# Keypad.net
KiCad netlist of a schematic drawn in Altium Designer
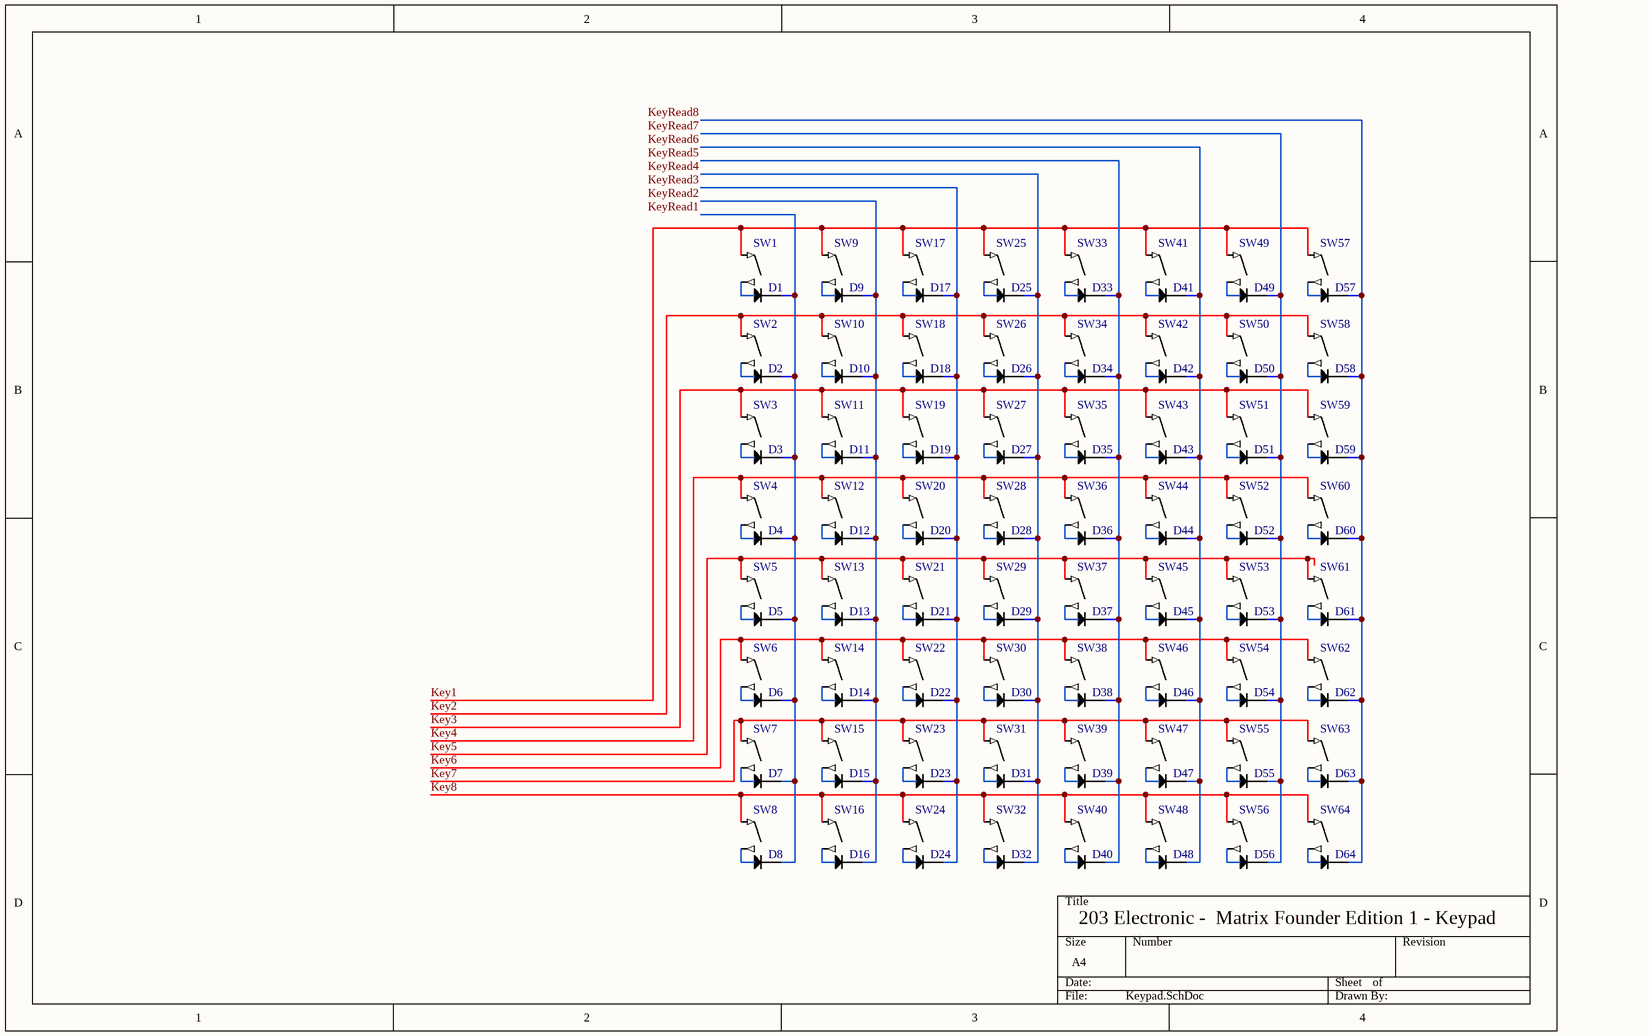
[diagram p0: Keypad.SchDoc]

(export (version "E")
  (design (tool "Eeschema 10.0.6"))
  (components
    (comp (ref "D1") (value "1N4148") (footprint "SOD123") (libsource (lib "Project 64") (part "1N4148")))
    (comp (ref "D2") (value "1N4148") (footprint "SOD123") (libsource (lib "Project 64") (part "1N4148")))
    (comp (ref "D3") (value "1N4148") (footprint "SOD123") (libsource (lib "Project 64") (part "1N4148")))
    (comp (ref "D4") (value "1N4148") (footprint "SOD123") (libsource (lib "Project 64") (part "1N4148")))
    (comp (ref "D5") (value "1N4148") (footprint "SOD123") (libsource (lib "Project 64") (part "1N4148")))
    (comp (ref "D6") (value "1N4148") (footprint "SOD123") (libsource (lib "Project 64") (part "1N4148")))
    (comp (ref "D7") (value "1N4148") (footprint "SOD123") (libsource (lib "Project 64") (part "1N4148")))
    (comp (ref "D8") (value "1N4148") (footprint "SOD123") (libsource (lib "Project 64") (part "1N4148")))
    (comp (ref "D9") (value "1N4148") (footprint "SOD123") (libsource (lib "Project 64") (part "1N4148")))
    (comp (ref "D10") (value "1N4148") (footprint "SOD123") (libsource (lib "Project 64") (part "1N4148")))
    (comp (ref "D11") (value "1N4148") (footprint "SOD123") (libsource (lib "Project 64") (part "1N4148")))
    (comp (ref "D12") (value "1N4148") (footprint "SOD123") (libsource (lib "Project 64") (part "1N4148")))
    (comp (ref "D13") (value "1N4148") (footprint "SOD123") (libsource (lib "Project 64") (part "1N4148")))
    (comp (ref "D14") (value "1N4148") (footprint "SOD123") (libsource (lib "Project 64") (part "1N4148")))
    (comp (ref "D15") (value "1N4148") (footprint "SOD123") (libsource (lib "Project 64") (part "1N4148")))
    (comp (ref "D16") (value "1N4148") (footprint "SOD123") (libsource (lib "Project 64") (part "1N4148")))
    (comp (ref "D17") (value "1N4148") (footprint "SOD123") (libsource (lib "Project 64") (part "1N4148")))
    (comp (ref "D18") (value "1N4148") (footprint "SOD123") (libsource (lib "Project 64") (part "1N4148")))
    (comp (ref "D19") (value "1N4148") (footprint "SOD123") (libsource (lib "Project 64") (part "1N4148")))
    (comp (ref "D20") (value "1N4148") (footprint "SOD123") (libsource (lib "Project 64") (part "1N4148")))
    (comp (ref "D21") (value "1N4148") (footprint "SOD123") (libsource (lib "Project 64") (part "1N4148")))
    (comp (ref "D22") (value "1N4148") (footprint "SOD123") (libsource (lib "Project 64") (part "1N4148")))
    (comp (ref "D23") (value "1N4148") (footprint "SOD123") (libsource (lib "Project 64") (part "1N4148")))
    (comp (ref "D24") (value "1N4148") (footprint "SOD123") (libsource (lib "Project 64") (part "1N4148")))
    (comp (ref "D25") (value "1N4148") (footprint "SOD123") (libsource (lib "Project 64") (part "1N4148")))
    (comp (ref "D26") (value "1N4148") (footprint "SOD123") (libsource (lib "Project 64") (part "1N4148")))
    (comp (ref "D27") (value "1N4148") (footprint "SOD123") (libsource (lib "Project 64") (part "1N4148")))
    (comp (ref "D28") (value "1N4148") (footprint "SOD123") (libsource (lib "Project 64") (part "1N4148")))
    (comp (ref "D29") (value "1N4148") (footprint "SOD123") (libsource (lib "Project 64") (part "1N4148")))
    (comp (ref "D30") (value "1N4148") (footprint "SOD123") (libsource (lib "Project 64") (part "1N4148")))
    (comp (ref "D31") (value "1N4148") (footprint "SOD123") (libsource (lib "Project 64") (part "1N4148")))
    (comp (ref "D32") (value "1N4148") (footprint "SOD123") (libsource (lib "Project 64") (part "1N4148")))
    (comp (ref "D33") (value "1N4148") (footprint "SOD123") (libsource (lib "Project 64") (part "1N4148")))
    (comp (ref "D34") (value "1N4148") (footprint "SOD123") (libsource (lib "Project 64") (part "1N4148")))
    (comp (ref "D35") (value "1N4148") (footprint "SOD123") (libsource (lib "Project 64") (part "1N4148")))
    (comp (ref "D36") (value "1N4148") (footprint "SOD123") (libsource (lib "Project 64") (part "1N4148")))
    (comp (ref "D37") (value "1N4148") (footprint "SOD123") (libsource (lib "Project 64") (part "1N4148")))
    (comp (ref "D38") (value "1N4148") (footprint "SOD123") (libsource (lib "Project 64") (part "1N4148")))
    (comp (ref "D39") (value "1N4148") (footprint "SOD123") (libsource (lib "Project 64") (part "1N4148")))
    (comp (ref "D40") (value "1N4148") (footprint "SOD123") (libsource (lib "Project 64") (part "1N4148")))
    (comp (ref "D41") (value "1N4148") (footprint "SOD123") (libsource (lib "Project 64") (part "1N4148")))
    (comp (ref "D42") (value "1N4148") (footprint "SOD123") (libsource (lib "Project 64") (part "1N4148")))
    (comp (ref "D43") (value "1N4148") (footprint "SOD123") (libsource (lib "Project 64") (part "1N4148")))
    (comp (ref "D44") (value "1N4148") (footprint "SOD123") (libsource (lib "Project 64") (part "1N4148")))
    (comp (ref "D45") (value "1N4148") (footprint "SOD123") (libsource (lib "Project 64") (part "1N4148")))
    (comp (ref "D46") (value "1N4148") (footprint "SOD123") (libsource (lib "Project 64") (part "1N4148")))
    (comp (ref "D47") (value "1N4148") (footprint "SOD123") (libsource (lib "Project 64") (part "1N4148")))
    (comp (ref "D48") (value "1N4148") (footprint "SOD123") (libsource (lib "Project 64") (part "1N4148")))
    (comp (ref "D49") (value "1N4148") (footprint "SOD123") (libsource (lib "Project 64") (part "1N4148")))
    (comp (ref "D50") (value "1N4148") (footprint "SOD123") (libsource (lib "Project 64") (part "1N4148")))
    (comp (ref "D51") (value "1N4148") (footprint "SOD123") (libsource (lib "Project 64") (part "1N4148")))
    (comp (ref "D52") (value "1N4148") (footprint "SOD123") (libsource (lib "Project 64") (part "1N4148")))
    (comp (ref "D53") (value "1N4148") (footprint "SOD123") (libsource (lib "Project 64") (part "1N4148")))
    (comp (ref "D54") (value "1N4148") (footprint "SOD123") (libsource (lib "Project 64") (part "1N4148")))
    (comp (ref "D55") (value "1N4148") (footprint "SOD123") (libsource (lib "Project 64") (part "1N4148")))
    (comp (ref "D56") (value "1N4148") (footprint "SOD123") (libsource (lib "Project 64") (part "1N4148")))
    (comp (ref "D57") (value "1N4148") (footprint "SOD123") (libsource (lib "Project 64") (part "1N4148")))
    (comp (ref "D58") (value "1N4148") (footprint "SOD123") (libsource (lib "Project 64") (part "1N4148")))
    (comp (ref "D59") (value "1N4148") (footprint "SOD123") (libsource (lib "Project 64") (part "1N4148")))
    (comp (ref "D60") (value "1N4148") (footprint "SOD123") (libsource (lib "Project 64") (part "1N4148")))
    (comp (ref "D61") (value "1N4148") (footprint "SOD123") (libsource (lib "Project 64") (part "1N4148")))
    (comp (ref "D62") (value "1N4148") (footprint "SOD123") (libsource (lib "Project 64") (part "1N4148")))
    (comp (ref "D63") (value "1N4148") (footprint "SOD123") (libsource (lib "Project 64") (part "1N4148")))
    (comp (ref "D64") (value "1N4148") (footprint "SOD123") (libsource (lib "Project 64") (part "1N4148")))
    (comp (ref "SW1") (value "~") (footprint "PAD") (libsource (lib "Project 64") (part "SW")))
    (comp (ref "SW2") (value "~") (footprint "PAD") (libsource (lib "Project 64") (part "SW")))
    (comp (ref "SW3") (value "~") (footprint "PAD") (libsource (lib "Project 64") (part "SW")))
    (comp (ref "SW4") (value "~") (footprint "PAD") (libsource (lib "Project 64") (part "SW")))
    (comp (ref "SW5") (value "~") (footprint "PAD") (libsource (lib "Project 64") (part "SW")))
    (comp (ref "SW6") (value "~") (footprint "PAD") (libsource (lib "Project 64") (part "SW")))
    (comp (ref "SW7") (value "~") (footprint "PAD") (libsource (lib "Project 64") (part "SW")))
    (comp (ref "SW8") (value "~") (footprint "PAD") (libsource (lib "Project 64") (part "SW")))
    (comp (ref "SW9") (value "~") (footprint "PAD") (libsource (lib "Project 64") (part "SW")))
    (comp (ref "SW10") (value "~") (footprint "PAD") (libsource (lib "Project 64") (part "SW")))
    (comp (ref "SW11") (value "~") (footprint "PAD") (libsource (lib "Project 64") (part "SW")))
    (comp (ref "SW12") (value "~") (footprint "PAD") (libsource (lib "Project 64") (part "SW")))
    (comp (ref "SW13") (value "~") (footprint "PAD") (libsource (lib "Project 64") (part "SW")))
    (comp (ref "SW14") (value "~") (footprint "PAD") (libsource (lib "Project 64") (part "SW")))
    (comp (ref "SW15") (value "~") (footprint "PAD") (libsource (lib "Project 64") (part "SW")))
    (comp (ref "SW16") (value "~") (footprint "PAD") (libsource (lib "Project 64") (part "SW")))
    (comp (ref "SW17") (value "~") (footprint "PAD") (libsource (lib "Project 64") (part "SW")))
    (comp (ref "SW18") (value "~") (footprint "PAD") (libsource (lib "Project 64") (part "SW")))
    (comp (ref "SW19") (value "~") (footprint "PAD") (libsource (lib "Project 64") (part "SW")))
    (comp (ref "SW20") (value "~") (footprint "PAD") (libsource (lib "Project 64") (part "SW")))
    (comp (ref "SW21") (value "~") (footprint "PAD") (libsource (lib "Project 64") (part "SW")))
    (comp (ref "SW22") (value "~") (footprint "PAD") (libsource (lib "Project 64") (part "SW")))
    (comp (ref "SW23") (value "~") (footprint "PAD") (libsource (lib "Project 64") (part "SW")))
    (comp (ref "SW24") (value "~") (footprint "PAD") (libsource (lib "Project 64") (part "SW")))
    (comp (ref "SW25") (value "~") (footprint "PAD") (libsource (lib "Project 64") (part "SW")))
    (comp (ref "SW26") (value "~") (footprint "PAD") (libsource (lib "Project 64") (part "SW")))
    (comp (ref "SW27") (value "~") (footprint "PAD") (libsource (lib "Project 64") (part "SW")))
    (comp (ref "SW28") (value "~") (footprint "PAD") (libsource (lib "Project 64") (part "SW")))
    (comp (ref "SW29") (value "~") (footprint "PAD") (libsource (lib "Project 64") (part "SW")))
    (comp (ref "SW30") (value "~") (footprint "PAD") (libsource (lib "Project 64") (part "SW")))
    (comp (ref "SW31") (value "~") (footprint "PAD") (libsource (lib "Project 64") (part "SW")))
    (comp (ref "SW32") (value "~") (footprint "PAD") (libsource (lib "Project 64") (part "SW")))
    (comp (ref "SW33") (value "~") (footprint "PAD") (libsource (lib "Project 64") (part "SW")))
    (comp (ref "SW34") (value "~") (footprint "PAD") (libsource (lib "Project 64") (part "SW")))
    (comp (ref "SW35") (value "~") (footprint "PAD") (libsource (lib "Project 64") (part "SW")))
    (comp (ref "SW36") (value "~") (footprint "PAD") (libsource (lib "Project 64") (part "SW")))
    (comp (ref "SW37") (value "~") (footprint "PAD") (libsource (lib "Project 64") (part "SW")))
    (comp (ref "SW38") (value "~") (footprint "PAD") (libsource (lib "Project 64") (part "SW")))
    (comp (ref "SW39") (value "~") (footprint "PAD") (libsource (lib "Project 64") (part "SW")))
    (comp (ref "SW40") (value "~") (footprint "PAD") (libsource (lib "Project 64") (part "SW")))
    (comp (ref "SW41") (value "~") (footprint "PAD") (libsource (lib "Project 64") (part "SW")))
    (comp (ref "SW42") (value "~") (footprint "PAD") (libsource (lib "Project 64") (part "SW")))
    (comp (ref "SW43") (value "~") (footprint "PAD") (libsource (lib "Project 64") (part "SW")))
    (comp (ref "SW44") (value "~") (footprint "PAD") (libsource (lib "Project 64") (part "SW")))
    (comp (ref "SW45") (value "~") (footprint "PAD") (libsource (lib "Project 64") (part "SW")))
    (comp (ref "SW46") (value "~") (footprint "PAD") (libsource (lib "Project 64") (part "SW")))
    (comp (ref "SW47") (value "~") (footprint "PAD") (libsource (lib "Project 64") (part "SW")))
    (comp (ref "SW48") (value "~") (footprint "PAD") (libsource (lib "Project 64") (part "SW")))
    (comp (ref "SW49") (value "~") (footprint "PAD") (libsource (lib "Project 64") (part "SW")))
    (comp (ref "SW50") (value "~") (footprint "PAD") (libsource (lib "Project 64") (part "SW")))
    (comp (ref "SW51") (value "~") (footprint "PAD") (libsource (lib "Project 64") (part "SW")))
    (comp (ref "SW52") (value "~") (footprint "PAD") (libsource (lib "Project 64") (part "SW")))
    (comp (ref "SW53") (value "~") (footprint "PAD") (libsource (lib "Project 64") (part "SW")))
    (comp (ref "SW54") (value "~") (footprint "PAD") (libsource (lib "Project 64") (part "SW")))
    (comp (ref "SW55") (value "~") (footprint "PAD") (libsource (lib "Project 64") (part "SW")))
    (comp (ref "SW56") (value "~") (footprint "PAD") (libsource (lib "Project 64") (part "SW")))
    (comp (ref "SW57") (value "~") (footprint "PAD") (libsource (lib "Project 64") (part "SW")))
    (comp (ref "SW58") (value "~") (footprint "PAD") (libsource (lib "Project 64") (part "SW")))
    (comp (ref "SW59") (value "~") (footprint "PAD") (libsource (lib "Project 64") (part "SW")))
    (comp (ref "SW60") (value "~") (footprint "PAD") (libsource (lib "Project 64") (part "SW")))
    (comp (ref "SW61") (value "~") (footprint "PAD") (libsource (lib "Project 64") (part "SW")))
    (comp (ref "SW62") (value "~") (footprint "PAD") (libsource (lib "Project 64") (part "SW")))
    (comp (ref "SW63") (value "~") (footprint "PAD") (libsource (lib "Project 64") (part "SW")))
    (comp (ref "SW64") (value "~") (footprint "PAD") (libsource (lib "Project 64") (part "SW")))
  )
  (nets
    (net (code "1") (name "/Key1") (class "Default")
      (node (ref "SW1") (pin "1") (pinfunction "1_1") (pintype "input"))
      (node (ref "SW17") (pin "1") (pinfunction "1_1") (pintype "input"))
      (node (ref "SW25") (pin "1") (pinfunction "1_1") (pintype "input"))
      (node (ref "SW33") (pin "1") (pinfunction "1_1") (pintype "input"))
      (node (ref "SW41") (pin "1") (pinfunction "1_1") (pintype "input"))
      (node (ref "SW49") (pin "1") (pinfunction "1_1") (pintype "input"))
      (node (ref "SW57") (pin "1") (pinfunction "1_1") (pintype "input"))
      (node (ref "SW9") (pin "1") (pinfunction "1_1") (pintype "input"))
    )
    (net (code "2") (name "/Key2") (class "Default")
      (node (ref "SW10") (pin "1") (pinfunction "1_1") (pintype "input"))
      (node (ref "SW18") (pin "1") (pinfunction "1_1") (pintype "input"))
      (node (ref "SW2") (pin "1") (pinfunction "1_1") (pintype "input"))
      (node (ref "SW26") (pin "1") (pinfunction "1_1") (pintype "input"))
      (node (ref "SW34") (pin "1") (pinfunction "1_1") (pintype "input"))
      (node (ref "SW42") (pin "1") (pinfunction "1_1") (pintype "input"))
      (node (ref "SW50") (pin "1") (pinfunction "1_1") (pintype "input"))
      (node (ref "SW58") (pin "1") (pinfunction "1_1") (pintype "input"))
    )
    (net (code "3") (name "/Key3") (class "Default")
      (node (ref "SW11") (pin "1") (pinfunction "1_1") (pintype "input"))
      (node (ref "SW19") (pin "1") (pinfunction "1_1") (pintype "input"))
      (node (ref "SW27") (pin "1") (pinfunction "1_1") (pintype "input"))
      (node (ref "SW3") (pin "1") (pinfunction "1_1") (pintype "input"))
      (node (ref "SW35") (pin "1") (pinfunction "1_1") (pintype "input"))
      (node (ref "SW43") (pin "1") (pinfunction "1_1") (pintype "input"))
      (node (ref "SW51") (pin "1") (pinfunction "1_1") (pintype "input"))
      (node (ref "SW59") (pin "1") (pinfunction "1_1") (pintype "input"))
    )
    (net (code "4") (name "/Key4") (class "Default")
      (node (ref "SW12") (pin "1") (pinfunction "1_1") (pintype "input"))
      (node (ref "SW20") (pin "1") (pinfunction "1_1") (pintype "input"))
      (node (ref "SW28") (pin "1") (pinfunction "1_1") (pintype "input"))
      (node (ref "SW36") (pin "1") (pinfunction "1_1") (pintype "input"))
      (node (ref "SW4") (pin "1") (pinfunction "1_1") (pintype "input"))
      (node (ref "SW44") (pin "1") (pinfunction "1_1") (pintype "input"))
      (node (ref "SW52") (pin "1") (pinfunction "1_1") (pintype "input"))
      (node (ref "SW60") (pin "1") (pinfunction "1_1") (pintype "input"))
    )
    (net (code "5") (name "/Key5") (class "Default")
      (node (ref "SW13") (pin "1") (pinfunction "1_1") (pintype "input"))
      (node (ref "SW21") (pin "1") (pinfunction "1_1") (pintype "input"))
      (node (ref "SW29") (pin "1") (pinfunction "1_1") (pintype "input"))
      (node (ref "SW37") (pin "1") (pinfunction "1_1") (pintype "input"))
      (node (ref "SW45") (pin "1") (pinfunction "1_1") (pintype "input"))
      (node (ref "SW5") (pin "1") (pinfunction "1_1") (pintype "input"))
      (node (ref "SW53") (pin "1") (pinfunction "1_1") (pintype "input"))
      (node (ref "SW61") (pin "1") (pinfunction "1_1") (pintype "input"))
    )
    (net (code "6") (name "/Key6") (class "Default")
      (node (ref "SW14") (pin "1") (pinfunction "1_1") (pintype "input"))
      (node (ref "SW22") (pin "1") (pinfunction "1_1") (pintype "input"))
      (node (ref "SW30") (pin "1") (pinfunction "1_1") (pintype "input"))
      (node (ref "SW38") (pin "1") (pinfunction "1_1") (pintype "input"))
      (node (ref "SW46") (pin "1") (pinfunction "1_1") (pintype "input"))
      (node (ref "SW54") (pin "1") (pinfunction "1_1") (pintype "input"))
      (node (ref "SW6") (pin "1") (pinfunction "1_1") (pintype "input"))
      (node (ref "SW62") (pin "1") (pinfunction "1_1") (pintype "input"))
    )
    (net (code "7") (name "/Key7") (class "Default")
      (node (ref "SW15") (pin "1") (pinfunction "1_1") (pintype "input"))
      (node (ref "SW23") (pin "1") (pinfunction "1_1") (pintype "input"))
      (node (ref "SW31") (pin "1") (pinfunction "1_1") (pintype "input"))
      (node (ref "SW39") (pin "1") (pinfunction "1_1") (pintype "input"))
      (node (ref "SW47") (pin "1") (pinfunction "1_1") (pintype "input"))
      (node (ref "SW55") (pin "1") (pinfunction "1_1") (pintype "input"))
      (node (ref "SW63") (pin "1") (pinfunction "1_1") (pintype "input"))
      (node (ref "SW7") (pin "1") (pinfunction "1_1") (pintype "input"))
    )
    (net (code "8") (name "/Key8") (class "Default")
      (node (ref "SW16") (pin "1") (pinfunction "1_1") (pintype "input"))
      (node (ref "SW24") (pin "1") (pinfunction "1_1") (pintype "input"))
      (node (ref "SW32") (pin "1") (pinfunction "1_1") (pintype "input"))
      (node (ref "SW40") (pin "1") (pinfunction "1_1") (pintype "input"))
      (node (ref "SW48") (pin "1") (pinfunction "1_1") (pintype "input"))
      (node (ref "SW56") (pin "1") (pinfunction "1_1") (pintype "input"))
      (node (ref "SW64") (pin "1") (pinfunction "1_1") (pintype "input"))
      (node (ref "SW8") (pin "1") (pinfunction "1_1") (pintype "input"))
    )
    (net (code "9") (name "/KeyRead1") (class "Default")
      (node (ref "D1") (pin "2") (pinfunction "2_2") (pintype "passive"))
      (node (ref "D2") (pin "2") (pinfunction "2_2") (pintype "passive"))
      (node (ref "D3") (pin "2") (pinfunction "2_2") (pintype "passive"))
      (node (ref "D4") (pin "2") (pinfunction "2_2") (pintype "passive"))
      (node (ref "D5") (pin "2") (pinfunction "2_2") (pintype "passive"))
      (node (ref "D6") (pin "2") (pinfunction "2_2") (pintype "passive"))
      (node (ref "D7") (pin "2") (pinfunction "2_2") (pintype "passive"))
      (node (ref "D8") (pin "2") (pinfunction "2_2") (pintype "passive"))
    )
    (net (code "10") (name "/KeyRead2") (class "Default")
      (node (ref "D10") (pin "2") (pinfunction "2_2") (pintype "passive"))
      (node (ref "D11") (pin "2") (pinfunction "2_2") (pintype "passive"))
      (node (ref "D12") (pin "2") (pinfunction "2_2") (pintype "passive"))
      (node (ref "D13") (pin "2") (pinfunction "2_2") (pintype "passive"))
      (node (ref "D14") (pin "2") (pinfunction "2_2") (pintype "passive"))
      (node (ref "D15") (pin "2") (pinfunction "2_2") (pintype "passive"))
      (node (ref "D16") (pin "2") (pinfunction "2_2") (pintype "passive"))
      (node (ref "D9") (pin "2") (pinfunction "2_2") (pintype "passive"))
    )
    (net (code "11") (name "/KeyRead3") (class "Default")
      (node (ref "D17") (pin "2") (pinfunction "2_2") (pintype "passive"))
      (node (ref "D18") (pin "2") (pinfunction "2_2") (pintype "passive"))
      (node (ref "D19") (pin "2") (pinfunction "2_2") (pintype "passive"))
      (node (ref "D20") (pin "2") (pinfunction "2_2") (pintype "passive"))
      (node (ref "D21") (pin "2") (pinfunction "2_2") (pintype "passive"))
      (node (ref "D22") (pin "2") (pinfunction "2_2") (pintype "passive"))
      (node (ref "D23") (pin "2") (pinfunction "2_2") (pintype "passive"))
      (node (ref "D24") (pin "2") (pinfunction "2_2") (pintype "passive"))
    )
    (net (code "12") (name "/KeyRead4") (class "Default")
      (node (ref "D25") (pin "2") (pinfunction "2_2") (pintype "passive"))
      (node (ref "D26") (pin "2") (pinfunction "2_2") (pintype "passive"))
      (node (ref "D27") (pin "2") (pinfunction "2_2") (pintype "passive"))
      (node (ref "D28") (pin "2") (pinfunction "2_2") (pintype "passive"))
      (node (ref "D29") (pin "2") (pinfunction "2_2") (pintype "passive"))
      (node (ref "D30") (pin "2") (pinfunction "2_2") (pintype "passive"))
      (node (ref "D31") (pin "2") (pinfunction "2_2") (pintype "passive"))
      (node (ref "D32") (pin "2") (pinfunction "2_2") (pintype "passive"))
    )
    (net (code "13") (name "/KeyRead5") (class "Default")
      (node (ref "D33") (pin "2") (pinfunction "2_2") (pintype "passive"))
      (node (ref "D34") (pin "2") (pinfunction "2_2") (pintype "passive"))
      (node (ref "D35") (pin "2") (pinfunction "2_2") (pintype "passive"))
      (node (ref "D36") (pin "2") (pinfunction "2_2") (pintype "passive"))
      (node (ref "D37") (pin "2") (pinfunction "2_2") (pintype "passive"))
      (node (ref "D38") (pin "2") (pinfunction "2_2") (pintype "passive"))
      (node (ref "D39") (pin "2") (pinfunction "2_2") (pintype "passive"))
      (node (ref "D40") (pin "2") (pinfunction "2_2") (pintype "passive"))
    )
    (net (code "14") (name "/KeyRead6") (class "Default")
      (node (ref "D41") (pin "2") (pinfunction "2_2") (pintype "passive"))
      (node (ref "D42") (pin "2") (pinfunction "2_2") (pintype "passive"))
      (node (ref "D43") (pin "2") (pinfunction "2_2") (pintype "passive"))
      (node (ref "D44") (pin "2") (pinfunction "2_2") (pintype "passive"))
      (node (ref "D45") (pin "2") (pinfunction "2_2") (pintype "passive"))
      (node (ref "D46") (pin "2") (pinfunction "2_2") (pintype "passive"))
      (node (ref "D47") (pin "2") (pinfunction "2_2") (pintype "passive"))
      (node (ref "D48") (pin "2") (pinfunction "2_2") (pintype "passive"))
    )
    (net (code "15") (name "/KeyRead7") (class "Default")
      (node (ref "D49") (pin "2") (pinfunction "2_2") (pintype "passive"))
      (node (ref "D50") (pin "2") (pinfunction "2_2") (pintype "passive"))
      (node (ref "D51") (pin "2") (pinfunction "2_2") (pintype "passive"))
      (node (ref "D52") (pin "2") (pinfunction "2_2") (pintype "passive"))
      (node (ref "D53") (pin "2") (pinfunction "2_2") (pintype "passive"))
      (node (ref "D54") (pin "2") (pinfunction "2_2") (pintype "passive"))
      (node (ref "D55") (pin "2") (pinfunction "2_2") (pintype "passive"))
      (node (ref "D56") (pin "2") (pinfunction "2_2") (pintype "passive"))
    )
    (net (code "16") (name "/KeyRead8") (class "Default")
      (node (ref "D57") (pin "2") (pinfunction "2_2") (pintype "passive"))
      (node (ref "D58") (pin "2") (pinfunction "2_2") (pintype "passive"))
      (node (ref "D59") (pin "2") (pinfunction "2_2") (pintype "passive"))
      (node (ref "D60") (pin "2") (pinfunction "2_2") (pintype "passive"))
      (node (ref "D61") (pin "2") (pinfunction "2_2") (pintype "passive"))
      (node (ref "D62") (pin "2") (pinfunction "2_2") (pintype "passive"))
      (node (ref "D63") (pin "2") (pinfunction "2_2") (pintype "passive"))
      (node (ref "D64") (pin "2") (pinfunction "2_2") (pintype "passive"))
    )
    (net (code "17") (name "Net-(SW1-Out)") (class "Default")
      (node (ref "D1") (pin "1") (pinfunction "1_1") (pintype "passive"))
      (node (ref "SW1") (pin "2") (pinfunction "Out_2") (pintype "output"))
    )
    (net (code "18") (name "Net-(SW2-Out)") (class "Default")
      (node (ref "D2") (pin "1") (pinfunction "1_1") (pintype "passive"))
      (node (ref "SW2") (pin "2") (pinfunction "Out_2") (pintype "output"))
    )
    (net (code "19") (name "Net-(SW3-Out)") (class "Default")
      (node (ref "D3") (pin "1") (pinfunction "1_1") (pintype "passive"))
      (node (ref "SW3") (pin "2") (pinfunction "Out_2") (pintype "output"))
    )
    (net (code "20") (name "Net-(SW4-Out)") (class "Default")
      (node (ref "D4") (pin "1") (pinfunction "1_1") (pintype "passive"))
      (node (ref "SW4") (pin "2") (pinfunction "Out_2") (pintype "output"))
    )
    (net (code "21") (name "Net-(SW5-Out)") (class "Default")
      (node (ref "D5") (pin "1") (pinfunction "1_1") (pintype "passive"))
      (node (ref "SW5") (pin "2") (pinfunction "Out_2") (pintype "output"))
    )
    (net (code "22") (name "Net-(SW6-Out)") (class "Default")
      (node (ref "D6") (pin "1") (pinfunction "1_1") (pintype "passive"))
      (node (ref "SW6") (pin "2") (pinfunction "Out_2") (pintype "output"))
    )
    (net (code "23") (name "Net-(SW7-Out)") (class "Default")
      (node (ref "D7") (pin "1") (pinfunction "1_1") (pintype "passive"))
      (node (ref "SW7") (pin "2") (pinfunction "Out_2") (pintype "output"))
    )
    (net (code "24") (name "Net-(SW8-Out)") (class "Default")
      (node (ref "D8") (pin "1") (pinfunction "1_1") (pintype "passive"))
      (node (ref "SW8") (pin "2") (pinfunction "Out_2") (pintype "output"))
    )
    (net (code "25") (name "Net-(SW9-Out)") (class "Default")
      (node (ref "D9") (pin "1") (pinfunction "1_1") (pintype "passive"))
      (node (ref "SW9") (pin "2") (pinfunction "Out_2") (pintype "output"))
    )
    (net (code "26") (name "Net-(SW10-Out)") (class "Default")
      (node (ref "D10") (pin "1") (pinfunction "1_1") (pintype "passive"))
      (node (ref "SW10") (pin "2") (pinfunction "Out_2") (pintype "output"))
    )
    (net (code "27") (name "Net-(SW11-Out)") (class "Default")
      (node (ref "D11") (pin "1") (pinfunction "1_1") (pintype "passive"))
      (node (ref "SW11") (pin "2") (pinfunction "Out_2") (pintype "output"))
    )
    (net (code "28") (name "Net-(SW12-Out)") (class "Default")
      (node (ref "D12") (pin "1") (pinfunction "1_1") (pintype "passive"))
      (node (ref "SW12") (pin "2") (pinfunction "Out_2") (pintype "output"))
    )
    (net (code "29") (name "Net-(SW13-Out)") (class "Default")
      (node (ref "D13") (pin "1") (pinfunction "1_1") (pintype "passive"))
      (node (ref "SW13") (pin "2") (pinfunction "Out_2") (pintype "output"))
    )
    (net (code "30") (name "Net-(SW14-Out)") (class "Default")
      (node (ref "D14") (pin "1") (pinfunction "1_1") (pintype "passive"))
      (node (ref "SW14") (pin "2") (pinfunction "Out_2") (pintype "output"))
    )
    (net (code "31") (name "Net-(SW15-Out)") (class "Default")
      (node (ref "D15") (pin "1") (pinfunction "1_1") (pintype "passive"))
      (node (ref "SW15") (pin "2") (pinfunction "Out_2") (pintype "output"))
    )
    (net (code "32") (name "Net-(SW16-Out)") (class "Default")
      (node (ref "D16") (pin "1") (pinfunction "1_1") (pintype "passive"))
      (node (ref "SW16") (pin "2") (pinfunction "Out_2") (pintype "output"))
    )
    (net (code "33") (name "Net-(SW17-Out)") (class "Default")
      (node (ref "D17") (pin "1") (pinfunction "1_1") (pintype "passive"))
      (node (ref "SW17") (pin "2") (pinfunction "Out_2") (pintype "output"))
    )
    (net (code "34") (name "Net-(SW18-Out)") (class "Default")
      (node (ref "D18") (pin "1") (pinfunction "1_1") (pintype "passive"))
      (node (ref "SW18") (pin "2") (pinfunction "Out_2") (pintype "output"))
    )
    (net (code "35") (name "Net-(SW19-Out)") (class "Default")
      (node (ref "D19") (pin "1") (pinfunction "1_1") (pintype "passive"))
      (node (ref "SW19") (pin "2") (pinfunction "Out_2") (pintype "output"))
    )
    (net (code "36") (name "Net-(SW20-Out)") (class "Default")
      (node (ref "D20") (pin "1") (pinfunction "1_1") (pintype "passive"))
      (node (ref "SW20") (pin "2") (pinfunction "Out_2") (pintype "output"))
    )
    (net (code "37") (name "Net-(SW21-Out)") (class "Default")
      (node (ref "D21") (pin "1") (pinfunction "1_1") (pintype "passive"))
      (node (ref "SW21") (pin "2") (pinfunction "Out_2") (pintype "output"))
    )
    (net (code "38") (name "Net-(SW22-Out)") (class "Default")
      (node (ref "D22") (pin "1") (pinfunction "1_1") (pintype "passive"))
      (node (ref "SW22") (pin "2") (pinfunction "Out_2") (pintype "output"))
    )
    (net (code "39") (name "Net-(SW23-Out)") (class "Default")
      (node (ref "D23") (pin "1") (pinfunction "1_1") (pintype "passive"))
      (node (ref "SW23") (pin "2") (pinfunction "Out_2") (pintype "output"))
    )
    (net (code "40") (name "Net-(SW24-Out)") (class "Default")
      (node (ref "D24") (pin "1") (pinfunction "1_1") (pintype "passive"))
      (node (ref "SW24") (pin "2") (pinfunction "Out_2") (pintype "output"))
    )
    (net (code "41") (name "Net-(SW25-Out)") (class "Default")
      (node (ref "D25") (pin "1") (pinfunction "1_1") (pintype "passive"))
      (node (ref "SW25") (pin "2") (pinfunction "Out_2") (pintype "output"))
    )
    (net (code "42") (name "Net-(SW26-Out)") (class "Default")
      (node (ref "D26") (pin "1") (pinfunction "1_1") (pintype "passive"))
      (node (ref "SW26") (pin "2") (pinfunction "Out_2") (pintype "output"))
    )
    (net (code "43") (name "Net-(SW27-Out)") (class "Default")
      (node (ref "D27") (pin "1") (pinfunction "1_1") (pintype "passive"))
      (node (ref "SW27") (pin "2") (pinfunction "Out_2") (pintype "output"))
    )
    (net (code "44") (name "Net-(SW28-Out)") (class "Default")
      (node (ref "D28") (pin "1") (pinfunction "1_1") (pintype "passive"))
      (node (ref "SW28") (pin "2") (pinfunction "Out_2") (pintype "output"))
    )
    (net (code "45") (name "Net-(SW29-Out)") (class "Default")
      (node (ref "D29") (pin "1") (pinfunction "1_1") (pintype "passive"))
      (node (ref "SW29") (pin "2") (pinfunction "Out_2") (pintype "output"))
    )
    (net (code "46") (name "Net-(SW30-Out)") (class "Default")
      (node (ref "D30") (pin "1") (pinfunction "1_1") (pintype "passive"))
      (node (ref "SW30") (pin "2") (pinfunction "Out_2") (pintype "output"))
    )
    (net (code "47") (name "Net-(SW31-Out)") (class "Default")
      (node (ref "D31") (pin "1") (pinfunction "1_1") (pintype "passive"))
      (node (ref "SW31") (pin "2") (pinfunction "Out_2") (pintype "output"))
    )
    (net (code "48") (name "Net-(SW32-Out)") (class "Default")
      (node (ref "D32") (pin "1") (pinfunction "1_1") (pintype "passive"))
      (node (ref "SW32") (pin "2") (pinfunction "Out_2") (pintype "output"))
    )
    (net (code "49") (name "Net-(SW33-Out)") (class "Default")
      (node (ref "D33") (pin "1") (pinfunction "1_1") (pintype "passive"))
      (node (ref "SW33") (pin "2") (pinfunction "Out_2") (pintype "output"))
    )
    (net (code "50") (name "Net-(SW34-Out)") (class "Default")
      (node (ref "D34") (pin "1") (pinfunction "1_1") (pintype "passive"))
      (node (ref "SW34") (pin "2") (pinfunction "Out_2") (pintype "output"))
    )
    (net (code "51") (name "Net-(SW35-Out)") (class "Default")
      (node (ref "D35") (pin "1") (pinfunction "1_1") (pintype "passive"))
      (node (ref "SW35") (pin "2") (pinfunction "Out_2") (pintype "output"))
    )
    (net (code "52") (name "Net-(SW36-Out)") (class "Default")
      (node (ref "D36") (pin "1") (pinfunction "1_1") (pintype "passive"))
      (node (ref "SW36") (pin "2") (pinfunction "Out_2") (pintype "output"))
    )
    (net (code "53") (name "Net-(SW37-Out)") (class "Default")
      (node (ref "D37") (pin "1") (pinfunction "1_1") (pintype "passive"))
      (node (ref "SW37") (pin "2") (pinfunction "Out_2") (pintype "output"))
    )
    (net (code "54") (name "Net-(SW38-Out)") (class "Default")
      (node (ref "D38") (pin "1") (pinfunction "1_1") (pintype "passive"))
      (node (ref "SW38") (pin "2") (pinfunction "Out_2") (pintype "output"))
    )
    (net (code "55") (name "Net-(SW39-Out)") (class "Default")
      (node (ref "D39") (pin "1") (pinfunction "1_1") (pintype "passive"))
      (node (ref "SW39") (pin "2") (pinfunction "Out_2") (pintype "output"))
    )
    (net (code "56") (name "Net-(SW40-Out)") (class "Default")
      (node (ref "D40") (pin "1") (pinfunction "1_1") (pintype "passive"))
      (node (ref "SW40") (pin "2") (pinfunction "Out_2") (pintype "output"))
    )
    (net (code "57") (name "Net-(SW41-Out)") (class "Default")
      (node (ref "D41") (pin "1") (pinfunction "1_1") (pintype "passive"))
      (node (ref "SW41") (pin "2") (pinfunction "Out_2") (pintype "output"))
    )
    (net (code "58") (name "Net-(SW42-Out)") (class "Default")
      (node (ref "D42") (pin "1") (pinfunction "1_1") (pintype "passive"))
      (node (ref "SW42") (pin "2") (pinfunction "Out_2") (pintype "output"))
    )
    (net (code "59") (name "Net-(SW43-Out)") (class "Default")
      (node (ref "D43") (pin "1") (pinfunction "1_1") (pintype "passive"))
      (node (ref "SW43") (pin "2") (pinfunction "Out_2") (pintype "output"))
    )
    (net (code "60") (name "Net-(SW44-Out)") (class "Default")
      (node (ref "D44") (pin "1") (pinfunction "1_1") (pintype "passive"))
      (node (ref "SW44") (pin "2") (pinfunction "Out_2") (pintype "output"))
    )
    (net (code "61") (name "Net-(SW45-Out)") (class "Default")
      (node (ref "D45") (pin "1") (pinfunction "1_1") (pintype "passive"))
      (node (ref "SW45") (pin "2") (pinfunction "Out_2") (pintype "output"))
    )
    (net (code "62") (name "Net-(SW46-Out)") (class "Default")
      (node (ref "D46") (pin "1") (pinfunction "1_1") (pintype "passive"))
      (node (ref "SW46") (pin "2") (pinfunction "Out_2") (pintype "output"))
    )
    (net (code "63") (name "Net-(SW47-Out)") (class "Default")
      (node (ref "D47") (pin "1") (pinfunction "1_1") (pintype "passive"))
      (node (ref "SW47") (pin "2") (pinfunction "Out_2") (pintype "output"))
    )
    (net (code "64") (name "Net-(SW48-Out)") (class "Default")
      (node (ref "D48") (pin "1") (pinfunction "1_1") (pintype "passive"))
      (node (ref "SW48") (pin "2") (pinfunction "Out_2") (pintype "output"))
    )
    (net (code "65") (name "Net-(SW49-Out)") (class "Default")
      (node (ref "D49") (pin "1") (pinfunction "1_1") (pintype "passive"))
      (node (ref "SW49") (pin "2") (pinfunction "Out_2") (pintype "output"))
    )
    (net (code "66") (name "Net-(SW50-Out)") (class "Default")
      (node (ref "D50") (pin "1") (pinfunction "1_1") (pintype "passive"))
      (node (ref "SW50") (pin "2") (pinfunction "Out_2") (pintype "output"))
    )
    (net (code "67") (name "Net-(SW51-Out)") (class "Default")
      (node (ref "D51") (pin "1") (pinfunction "1_1") (pintype "passive"))
      (node (ref "SW51") (pin "2") (pinfunction "Out_2") (pintype "output"))
    )
    (net (code "68") (name "Net-(SW52-Out)") (class "Default")
      (node (ref "D52") (pin "1") (pinfunction "1_1") (pintype "passive"))
      (node (ref "SW52") (pin "2") (pinfunction "Out_2") (pintype "output"))
    )
    (net (code "69") (name "Net-(SW53-Out)") (class "Default")
      (node (ref "D53") (pin "1") (pinfunction "1_1") (pintype "passive"))
      (node (ref "SW53") (pin "2") (pinfunction "Out_2") (pintype "output"))
    )
    (net (code "70") (name "Net-(SW54-Out)") (class "Default")
      (node (ref "D54") (pin "1") (pinfunction "1_1") (pintype "passive"))
      (node (ref "SW54") (pin "2") (pinfunction "Out_2") (pintype "output"))
    )
    (net (code "71") (name "Net-(SW55-Out)") (class "Default")
      (node (ref "D55") (pin "1") (pinfunction "1_1") (pintype "passive"))
      (node (ref "SW55") (pin "2") (pinfunction "Out_2") (pintype "output"))
    )
    (net (code "72") (name "Net-(SW56-Out)") (class "Default")
      (node (ref "D56") (pin "1") (pinfunction "1_1") (pintype "passive"))
      (node (ref "SW56") (pin "2") (pinfunction "Out_2") (pintype "output"))
    )
    (net (code "73") (name "Net-(SW57-Out)") (class "Default")
      (node (ref "D57") (pin "1") (pinfunction "1_1") (pintype "passive"))
      (node (ref "SW57") (pin "2") (pinfunction "Out_2") (pintype "output"))
    )
    (net (code "74") (name "Net-(SW58-Out)") (class "Default")
      (node (ref "D58") (pin "1") (pinfunction "1_1") (pintype "passive"))
      (node (ref "SW58") (pin "2") (pinfunction "Out_2") (pintype "output"))
    )
    (net (code "75") (name "Net-(SW59-Out)") (class "Default")
      (node (ref "D59") (pin "1") (pinfunction "1_1") (pintype "passive"))
      (node (ref "SW59") (pin "2") (pinfunction "Out_2") (pintype "output"))
    )
    (net (code "76") (name "Net-(SW60-Out)") (class "Default")
      (node (ref "D60") (pin "1") (pinfunction "1_1") (pintype "passive"))
      (node (ref "SW60") (pin "2") (pinfunction "Out_2") (pintype "output"))
    )
    (net (code "77") (name "Net-(SW61-Out)") (class "Default")
      (node (ref "D61") (pin "1") (pinfunction "1_1") (pintype "passive"))
      (node (ref "SW61") (pin "2") (pinfunction "Out_2") (pintype "output"))
    )
    (net (code "78") (name "Net-(SW62-Out)") (class "Default")
      (node (ref "D62") (pin "1") (pinfunction "1_1") (pintype "passive"))
      (node (ref "SW62") (pin "2") (pinfunction "Out_2") (pintype "output"))
    )
    (net (code "79") (name "Net-(SW63-Out)") (class "Default")
      (node (ref "D63") (pin "1") (pinfunction "1_1") (pintype "passive"))
      (node (ref "SW63") (pin "2") (pinfunction "Out_2") (pintype "output"))
    )
    (net (code "80") (name "Net-(SW64-Out)") (class "Default")
      (node (ref "D64") (pin "1") (pinfunction "1_1") (pintype "passive"))
      (node (ref "SW64") (pin "2") (pinfunction "Out_2") (pintype "output"))
    )
  )
)
